# Plant.net
KiCad netlist of a schematic drawn in Altium Designer
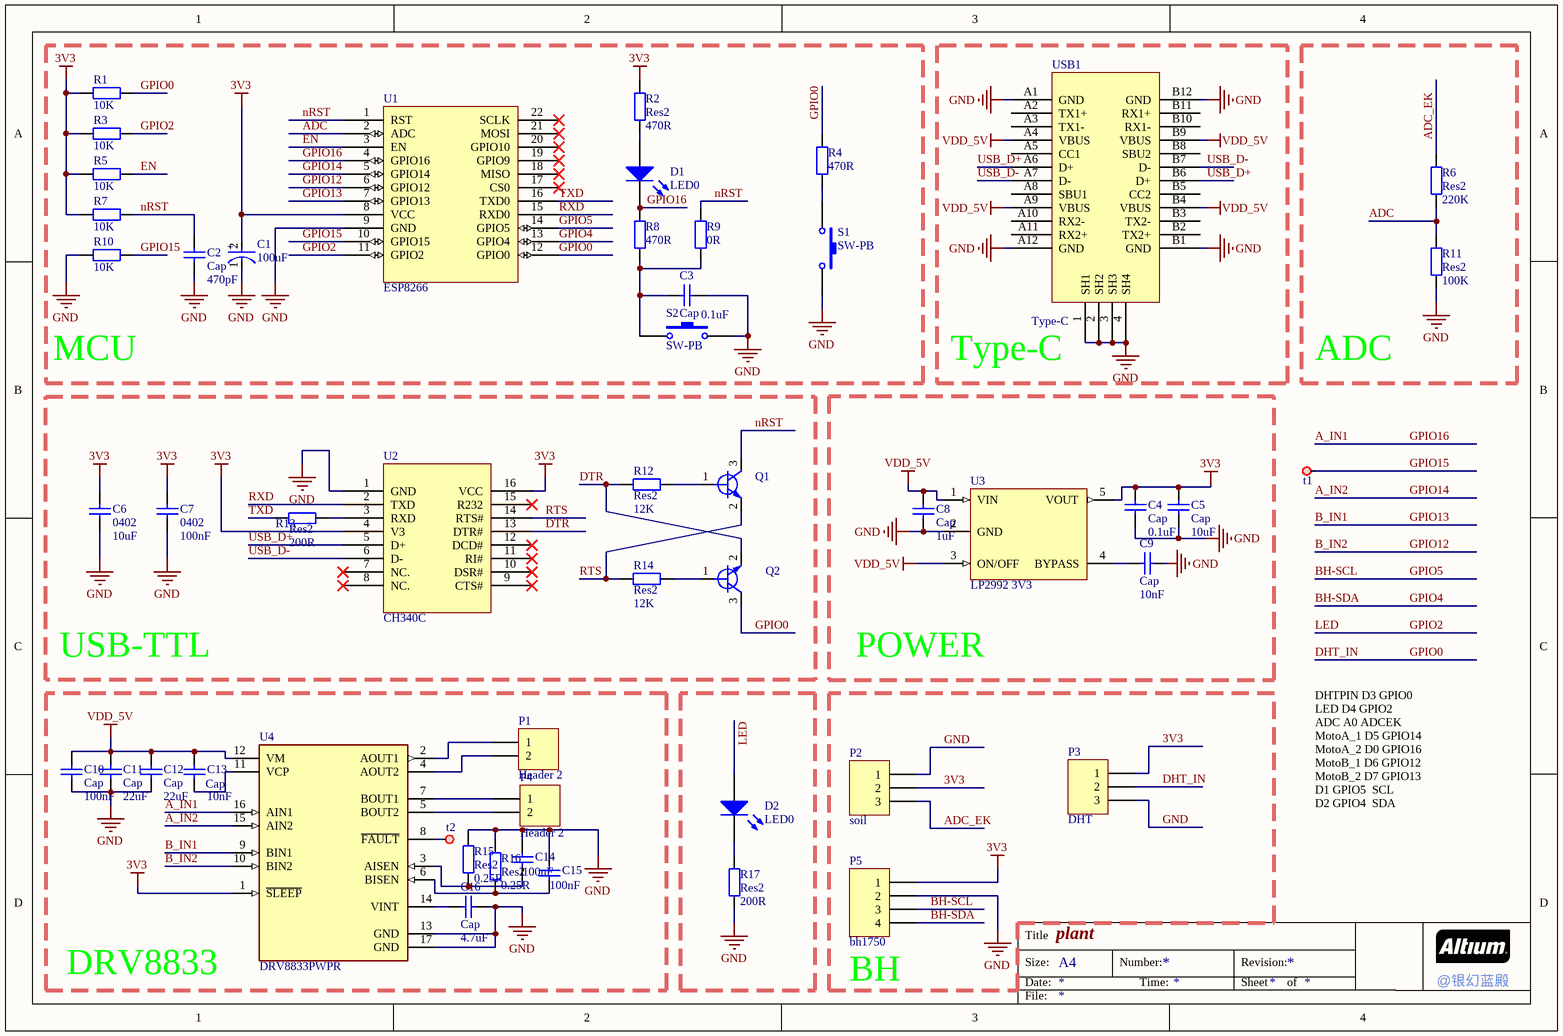
[diagram p0: Plant.SchDoc]

(export (version "E")
  (design (tool "Eeschema 10.0.6"))
  (components
    (comp (ref "C1")
      (value "100uF")
      (footprint "FP-T495D107K016ATE125-MFG")
      (description "CAP TANT 100UF 10% 16V 2917")
      (fields (field (name "VOLTAGE") "16V") (field (name "TOLERANCE") "10%"))
      (libsource (lib "Altium Content Vault") (part "a00bbbee19879c290e62620ae7e47b1"))
    )
    (comp (ref "C2")
      (value "Cap")
      (footprint "Plant:C 0402_M")
      (description "Capacitor (Semiconductor SIM Model)")
      (fields (field (name "ALTIUM_VALUE") "470pF") (field (name "PUBLISHER") "Altium Limited"))
      (libsource (lib "Miscellaneous Devices") (part "Cap Semi"))
    )
    (comp (ref "C3")
      (value "Cap")
      (footprint "Plant:C 0402_M")
      (description "Capacitor (Semiconductor SIM Model)")
      (fields (field (name "ALTIUM_VALUE") "0.1uF") (field (name "PUBLISHER") "Altium Limited"))
      (libsource (lib "Miscellaneous Devices") (part "Cap Semi"))
    )
    (comp (ref "C4")
      (value "Cap")
      (footprint "Plant:C 0402_M")
      (description "Capacitor (Semiconductor SIM Model)")
      (fields (field (name "ALTIUM_VALUE") "0.1uF") (field (name "PUBLISHER") "Altium Limited"))
      (libsource (lib "Miscellaneous Devices") (part "Cap Semi"))
    )
    (comp (ref "C5")
      (value "Cap")
      (footprint "Plant:C 0402_M")
      (description "Capacitor (Semiconductor SIM Model)")
      (fields (field (name "ALTIUM_VALUE") "10uF") (field (name "PUBLISHER") "Altium Limited"))
      (libsource (lib "Miscellaneous Devices") (part "Cap Semi"))
    )
    (comp (ref "C6")
      (value "0402")
      (footprint "Plant:C 0402_M")
      (description "Capacitor (Semiconductor SIM Model)")
      (fields (field (name "ALTIUM_VALUE") "10uF") (field (name "PUBLISHER") "Altium Limited"))
      (libsource (lib "Miscellaneous Devices") (part "Cap Semi"))
    )
    (comp (ref "C7")
      (value "0402")
      (footprint "Plant:C 0402_M")
      (description "Capacitor (Semiconductor SIM Model)")
      (fields (field (name "ALTIUM_VALUE") "100nF") (field (name "PUBLISHER") "Altium Limited"))
      (libsource (lib "Miscellaneous Devices") (part "Cap Semi"))
    )
    (comp (ref "C8")
      (value "Cap")
      (footprint "Plant:C 0402_M")
      (description "Capacitor (Semiconductor SIM Model)")
      (fields (field (name "ALTIUM_VALUE") "1uF") (field (name "PUBLISHER") "Altium Limited"))
      (libsource (lib "Miscellaneous Devices") (part "Cap Semi"))
    )
    (comp (ref "C9")
      (value "Cap")
      (footprint "Plant:C 0402_M")
      (description "Capacitor (Semiconductor SIM Model)")
      (fields (field (name "ALTIUM_VALUE") "10nF") (field (name "PUBLISHER") "Altium Limited"))
      (libsource (lib "Miscellaneous Devices") (part "Cap Semi"))
    )
    (comp (ref "C10")
      (value "Cap")
      (footprint "Plant:C 0402_M")
      (description "Capacitor (Semiconductor SIM Model)")
      (fields (field (name "ALTIUM_VALUE") "100nF") (field (name "PUBLISHER") "Altium Limited"))
      (libsource (lib "Miscellaneous Devices") (part "Cap Semi"))
    )
    (comp (ref "C11")
      (value "Cap")
      (footprint "Plant:C 0402_M")
      (description "Capacitor (Semiconductor SIM Model)")
      (fields (field (name "ALTIUM_VALUE") "22uF") (field (name "PUBLISHER") "Altium Limited"))
      (libsource (lib "Miscellaneous Devices") (part "Cap Semi"))
    )
    (comp (ref "C12")
      (value "Cap")
      (footprint "Plant:C 0402_M")
      (description "Capacitor (Semiconductor SIM Model)")
      (fields (field (name "ALTIUM_VALUE") "22uF") (field (name "PUBLISHER") "Altium Limited"))
      (libsource (lib "Miscellaneous Devices") (part "Cap Semi"))
    )
    (comp (ref "C13")
      (value "Cap")
      (footprint "Plant:C 0402_M")
      (description "Capacitor (Semiconductor SIM Model)")
      (fields (field (name "ALTIUM_VALUE") "10nF") (field (name "PUBLISHER") "Altium Limited"))
      (libsource (lib "Miscellaneous Devices") (part "Cap Semi"))
    )
    (comp (ref "C14")
      (value "100nF")
      (footprint "Plant:C 0402_M")
      (description "Capacitor (Semiconductor SIM Model)")
      (fields (field (name "PUBLISHER") "Altium Limited"))
      (libsource (lib "Miscellaneous Devices") (part "Cap Semi"))
    )
    (comp (ref "C15")
      (value "100nF")
      (footprint "Plant:C 0402_M")
      (description "Capacitor (Semiconductor SIM Model)")
      (fields (field (name "PUBLISHER") "Altium Limited"))
      (libsource (lib "Miscellaneous Devices") (part "Cap Semi"))
    )
    (comp (ref "C16")
      (value "Cap")
      (footprint "Plant:C 0402_M")
      (description "Capacitor (Semiconductor SIM Model)")
      (fields (field (name "ALTIUM_VALUE") "4.7uF") (field (name "PUBLISHER") "Altium Limited"))
      (libsource (lib "Miscellaneous Devices") (part "Cap Semi"))
    )
    (comp (ref "D1")
      (value "LED0")
      (footprint "LED 0603R")
      (description "Typical INFRARED GaAs LED")
      (fields (field (name "PUBLISHER") "Altium Limited"))
      (libsource (lib "Miscellaneous Devices") (part "LED0"))
    )
    (comp (ref "D2")
      (value "LED0")
      (footprint "LED 0603R")
      (description "Typical INFRARED GaAs LED")
      (fields (field (name "PUBLISHER") "Altium Limited"))
      (libsource (lib "Miscellaneous Devices") (part "LED0"))
    )
    (comp (ref "P1")
      (value "Header 2")
      (footprint "HDR1X2")
      (description "Header, 2-Pin")
      (fields (field (name "PUBLISHER") "Altium Limited"))
      (libsource (lib "Miscellaneous Connectors") (part "Header 2"))
    )
    (comp (ref "P2")
      (value "soil")
      (footprint "HDR1X3")
      (description "Header, 3-Pin")
      (fields (field (name "PUBLISHER") "Altium Limited"))
      (libsource (lib "Miscellaneous Connectors") (part "Header 3"))
    )
    (comp (ref "P3")
      (value "DHT")
      (footprint "HDR1X3")
      (description "Header, 3-Pin")
      (fields (field (name "PUBLISHER") "Altium Limited"))
      (libsource (lib "Miscellaneous Connectors") (part "Header 3"))
    )
    (comp (ref "P4")
      (value "Header 2")
      (footprint "HDR1X2")
      (description "Header, 2-Pin")
      (fields (field (name "PUBLISHER") "Altium Limited"))
      (libsource (lib "Miscellaneous Connectors") (part "Header 2"))
    )
    (comp (ref "P5")
      (value "bh1750")
      (footprint "HDR1X4")
      (description "Header, 4-Pin")
      (fields (field (name "PUBLISHER") "Altium Limited"))
      (libsource (lib "Miscellaneous Connectors") (part "Header 4"))
    )
    (comp (ref "Q1")
      (value "Y1 NPN SOT23-3")
      (footprint "SMT_TRIODE_NPN")
      (libsource (lib "DDJ_20180904_Library") (part "S8050"))
    )
    (comp (ref "Q2")
      (value "Y1 NPN SOT23-3")
      (footprint "SMT_TRIODE_NPN")
      (libsource (lib "DDJ_20180904_Library") (part "S8050"))
    )
    (comp (ref "R1")
      (value "10K")
      (footprint "Plant:R 0402_M")
      (description "Resistor")
      (fields (field (name "Comment") "0402") (field (name "PUBLISHER") "Altium Limited"))
      (libsource (lib "") (part "Res2_1"))
    )
    (comp (ref "R2")
      (value "Res2")
      (footprint "Plant:R 0402_M")
      (description "Resistor")
      (fields (field (name "ALTIUM_VALUE") "470R") (field (name "PUBLISHER") "Altium Limited"))
      (libsource (lib "Miscellaneous Devices") (part "Res2"))
    )
    (comp (ref "R3")
      (value "10K")
      (footprint "Plant:R 0402_M")
      (description "Resistor")
      (fields (field (name "Comment") "0402") (field (name "PUBLISHER") "Altium Limited"))
      (libsource (lib "") (part "Res2_1"))
    )
    (comp (ref "R4")
      (value "470R")
      (footprint "Plant:R 0402_M")
      (description "Resistor")
      (fields (field (name "Comment") "Res2") (field (name "PUBLISHER") "Altium Limited"))
      (libsource (lib "") (part "Res2_2"))
    )
    (comp (ref "R5")
      (value "10K")
      (footprint "Plant:R 0402_M")
      (description "Resistor")
      (fields (field (name "Comment") "0402") (field (name "PUBLISHER") "Altium Limited"))
      (libsource (lib "") (part "Res2_1"))
    )
    (comp (ref "R6")
      (value "Res2")
      (footprint "Plant:R 0402_M")
      (description "Resistor")
      (fields (field (name "ALTIUM_VALUE") "220K") (field (name "PUBLISHER") "Altium Limited"))
      (libsource (lib "Miscellaneous Devices") (part "Res2"))
    )
    (comp (ref "R7")
      (value "10K")
      (footprint "Plant:R 0402_M")
      (description "Resistor")
      (fields (field (name "Comment") "0402") (field (name "PUBLISHER") "Altium Limited"))
      (libsource (lib "") (part "Res2_1"))
    )
    (comp (ref "R8")
      (value "470R")
      (footprint "Plant:R 0402_M")
      (description "Resistor")
      (fields (field (name "Comment") "Res2") (field (name "PUBLISHER") "Altium Limited"))
      (libsource (lib "") (part "Res2_2"))
    )
    (comp (ref "R9")
      (value "0R")
      (footprint "Plant:R 0402_M")
      (description "Resistor")
      (fields (field (name "Comment") "Res2") (field (name "PUBLISHER") "Altium Limited"))
      (libsource (lib "") (part "Res2_2"))
    )
    (comp (ref "R10")
      (value "10K")
      (footprint "Plant:R 0402_M")
      (description "Resistor")
      (fields (field (name "Comment") "0402") (field (name "PUBLISHER") "Altium Limited"))
      (libsource (lib "") (part "Res2_1"))
    )
    (comp (ref "R11")
      (value "Res2")
      (footprint "Plant:R 0402_M")
      (description "Resistor")
      (fields (field (name "ALTIUM_VALUE") "100K") (field (name "PUBLISHER") "Altium Limited"))
      (libsource (lib "Miscellaneous Devices") (part "Res2"))
    )
    (comp (ref "R12")
      (value "Res2")
      (footprint "Plant:R 0402_M")
      (description "Resistor")
      (fields (field (name "ALTIUM_VALUE") "12K") (field (name "PUBLISHER") "Altium Limited"))
      (libsource (lib "") (part "Res2_1"))
    )
    (comp (ref "R13")
      (value "Res2")
      (footprint "Plant:R 0402_M")
      (description "Resistor")
      (fields (field (name "ALTIUM_VALUE") "200R") (field (name "PUBLISHER") "Altium Limited"))
      (libsource (lib "") (part "Res2_1"))
    )
    (comp (ref "R14")
      (value "Res2")
      (footprint "Plant:R 0402_M")
      (description "Resistor")
      (fields (field (name "ALTIUM_VALUE") "12K") (field (name "PUBLISHER") "Altium Limited"))
      (libsource (lib "") (part "Res2_1"))
    )
    (comp (ref "R15")
      (value "Res2")
      (footprint "Plant:R 1206_M")
      (description "Resistor")
      (fields (field (name "ALTIUM_VALUE") "0.25R") (field (name "PUBLISHER") "Altium Limited"))
      (libsource (lib "") (part "Res2_1"))
    )
    (comp (ref "R16")
      (value "Res2")
      (footprint "Plant:R 1206_M")
      (description "Resistor")
      (fields (field (name "ALTIUM_VALUE") "0.25R") (field (name "PUBLISHER") "Altium Limited"))
      (libsource (lib "") (part "Res2_1"))
    )
    (comp (ref "R17")
      (value "Res2")
      (footprint "Plant:R 0402_M")
      (description "Resistor")
      (fields (field (name "ALTIUM_VALUE") "200R") (field (name "PUBLISHER") "Altium Limited"))
      (libsource (lib "Miscellaneous Devices") (part "Res2"))
    )
    (comp (ref "S1")
      (value "SW-PB")
      (footprint "TSW DIP-6*6*5")
      (description "Switch")
      (fields (field (name "PUBLISHER") "Altium Limited"))
      (libsource (lib "Miscellaneous Devices") (part "SW-PB"))
    )
    (comp (ref "S2")
      (value "SW-PB")
      (footprint "TSW DIP-6*6*5")
      (description "Switch")
      (fields (field (name "PUBLISHER") "Altium Limited"))
      (libsource (lib "Miscellaneous Devices") (part "SW-PB"))
    )
    (comp (ref "t1") (value "test") (footprint "test") (libsource (lib "RC-AE86") (part "test")))
    (comp (ref "t2") (value "test") (footprint "test") (libsource (lib "RC-AE86") (part "test")))
    (comp (ref "U1") (value "ESP8266") (footprint "esp8266") (libsource (lib "HD") (part "ESP8266")))
    (comp (ref "U2") (value "CH340C") (footprint "CH340") (libsource (lib "HD") (part "CH340C")))
    (comp (ref "U3")
      (value "LP2992 3V3")
      (footprint "SOT23-5N")
      (description "LDO")
      (libsource (lib "MyPcbLib") (part "LP2992"))
    )
    (comp (ref "U4")
      (value "DRV8833PWPR")
      (footprint "FP-PWP0016C-IPC_A")
      (description "IC MOTOR DRIVER PAR 16HTSSOP")
      (libsource (lib "Altium Content Vault") (part "bca689d78e207bdabf30b9b31c2f798"))
    )
    (comp (ref "USB1")
      (value "Type-C")
      (footprint "Type-C-TOP")
      (libsource (lib "MainBoard") (part "USB-Type-C-TOP"))
    )
  )
  (nets
    (net (code "1") (name "/ADC") (class "Default")
      (node (ref "R11") (pin "1") (pinfunction "1_1") (pintype "passive"))
      (node (ref "R6") (pin "2") (pinfunction "2_2") (pintype "passive"))
      (node (ref "U1") (pin "2") (pinfunction "ADC_2") (pintype "bidirectional"))
    )
    (net (code "2") (name "/ADC_EK") (class "Default")
      (node (ref "P2") (pin "3") (pinfunction "3_3") (pintype "passive"))
      (node (ref "R6") (pin "1") (pinfunction "1_1") (pintype "passive"))
    )
    (net (code "3") (name "/A_IN1") (class "Default")
      (node (ref "D1") (pin "2") (pinfunction "K_2") (pintype "passive"))
      (node (ref "R8") (pin "2") (pinfunction "2_2") (pintype "passive"))
      (node (ref "U1") (pin "4") (pinfunction "GPIO16_4") (pintype "bidirectional"))
      (node (ref "U4") (pin "16") (pinfunction "AIN1_16") (pintype "input"))
    )
    (net (code "4") (name "/A_IN2") (class "Default")
      (node (ref "U1") (pin "5") (pinfunction "GPIO14_5") (pintype "bidirectional"))
      (node (ref "U4") (pin "15") (pinfunction "AIN2_15") (pintype "input"))
    )
    (net (code "5") (name "/BH-SCL") (class "Default")
      (node (ref "P5") (pin "3") (pinfunction "3_3") (pintype "passive"))
      (node (ref "U1") (pin "14") (pinfunction "GPIO5_14") (pintype "bidirectional"))
    )
    (net (code "6") (name "/BH-SDA") (class "Default")
      (node (ref "P5") (pin "4") (pinfunction "4_4") (pintype "passive"))
      (node (ref "U1") (pin "13") (pinfunction "GPIO4_13") (pintype "bidirectional"))
    )
    (net (code "7") (name "/B_IN1") (class "Default")
      (node (ref "U1") (pin "7") (pinfunction "GPIO13_7") (pintype "bidirectional"))
      (node (ref "U4") (pin "9") (pinfunction "BIN1_9") (pintype "input"))
    )
    (net (code "8") (name "/B_IN2") (class "Default")
      (node (ref "U1") (pin "6") (pinfunction "GPIO12_6") (pintype "bidirectional"))
      (node (ref "U4") (pin "10") (pinfunction "BIN2_10") (pintype "input"))
    )
    (net (code "9") (name "/DHT_IN") (class "Default")
      (node (ref "P3") (pin "2") (pinfunction "2_2") (pintype "passive"))
      (node (ref "Q2") (pin "3") (pinfunction "COLLECTOR_3") (pintype "passive"))
      (node (ref "R1") (pin "2") (pinfunction "2_2") (pintype "passive"))
      (node (ref "R4") (pin "2") (pinfunction "2_2") (pintype "passive"))
      (node (ref "U1") (pin "12") (pinfunction "GPIO0_12") (pintype "bidirectional"))
    )
    (net (code "10") (name "/DTR") (class "Default")
      (node (ref "Q2") (pin "2") (pinfunction "EMITTER_2") (pintype "passive"))
      (node (ref "R12") (pin "1") (pinfunction "1_1") (pintype "passive"))
      (node (ref "U2") (pin "13") (pinfunction "DTR#_13") (pintype "passive"))
    )
    (net (code "11") (name "/EN") (class "Default")
      (node (ref "R5") (pin "2") (pinfunction "2_2") (pintype "passive"))
      (node (ref "U1") (pin "3") (pinfunction "EN_3") (pintype "passive"))
    )
    (net (code "12") (name "/GPIO2") (class "Default")
      (node (ref "D2") (pin "1") (pinfunction "A_1") (pintype "passive"))
      (node (ref "R3") (pin "2") (pinfunction "2_2") (pintype "passive"))
      (node (ref "U1") (pin "11") (pinfunction "GPIO2_11") (pintype "bidirectional"))
    )
    (net (code "13") (name "/GPIO15") (class "Default")
      (node (ref "R10") (pin "2") (pinfunction "2_2") (pintype "passive"))
      (node (ref "U1") (pin "10") (pinfunction "GPIO15_10") (pintype "bidirectional"))
      (node (ref "t1") (pin "1") (pinfunction "test_1") (pintype "passive"))
    )
    (net (code "14") (name "/RTS") (class "Default")
      (node (ref "Q1") (pin "2") (pinfunction "EMITTER_2") (pintype "passive"))
      (node (ref "R14") (pin "1") (pinfunction "1_1") (pintype "passive"))
      (node (ref "U2") (pin "14") (pinfunction "RTS#_14") (pintype "passive"))
    )
    (net (code "15") (name "/RXD") (class "Default")
      (node (ref "U1") (pin "15") (pinfunction "RXD0_15") (pintype "passive"))
      (node (ref "U2") (pin "2") (pinfunction "TXD_2") (pintype "passive"))
    )
    (net (code "16") (name "/TXD") (class "Default")
      (node (ref "R13") (pin "1") (pinfunction "1_1") (pintype "passive"))
      (node (ref "U1") (pin "16") (pinfunction "TXD0_16") (pintype "passive"))
    )
    (net (code "17") (name "/USB_D+") (class "Default")
      (node (ref "U2") (pin "5") (pinfunction "D+_5") (pintype "passive"))
      (node (ref "USB1") (pin "A6") (pinfunction "D+_A6") (pintype "passive"))
      (node (ref "USB1") (pin "B6") (pinfunction "D+_B6") (pintype "passive"))
    )
    (net (code "18") (name "/USB_D-") (class "Default")
      (node (ref "U2") (pin "6") (pinfunction "D-_6") (pintype "passive"))
      (node (ref "USB1") (pin "A7") (pinfunction "D-_A7") (pintype "passive"))
      (node (ref "USB1") (pin "B7") (pinfunction "D-_B7") (pintype "passive"))
    )
    (net (code "19") (name "/nRST") (class "Default")
      (node (ref "C2") (pin "1") (pinfunction "1_1") (pintype "passive"))
      (node (ref "Q1") (pin "3") (pinfunction "COLLECTOR_3") (pintype "passive"))
      (node (ref "R7") (pin "2") (pinfunction "2_2") (pintype "passive"))
      (node (ref "R9") (pin "2") (pinfunction "2_2") (pintype "passive"))
      (node (ref "U1") (pin "1") (pinfunction "RST_1") (pintype "passive"))
    )
    (net (code "20") (name "3V3") (class "Default")
      (node (ref "C1") (pin "2") (pinfunction "A_2") (pintype "passive"))
      (node (ref "C4") (pin "1") (pinfunction "1_1") (pintype "passive"))
      (node (ref "C5") (pin "1") (pinfunction "1_1") (pintype "passive"))
      (node (ref "C6") (pin "2") (pinfunction "2_2") (pintype "passive"))
      (node (ref "C7") (pin "2") (pinfunction "2_2") (pintype "passive"))
      (node (ref "P2") (pin "2") (pinfunction "2_2") (pintype "passive"))
      (node (ref "P3") (pin "1") (pinfunction "1_1") (pintype "passive"))
      (node (ref "P5") (pin "1") (pinfunction "1_1") (pintype "passive"))
      (node (ref "R1") (pin "1") (pinfunction "1_1") (pintype "passive"))
      (node (ref "R2") (pin "1") (pinfunction "1_1") (pintype "passive"))
      (node (ref "R3") (pin "1") (pinfunction "1_1") (pintype "passive"))
      (node (ref "R5") (pin "1") (pinfunction "1_1") (pintype "passive"))
      (node (ref "R7") (pin "1") (pinfunction "1_1") (pintype "passive"))
      (node (ref "U1") (pin "8") (pinfunction "VCC_8") (pintype "passive"))
      (node (ref "U2") (pin "16") (pinfunction "VCC_16") (pintype "passive"))
      (node (ref "U2") (pin "4") (pinfunction "V3_4") (pintype "passive"))
      (node (ref "U3") (pin "5") (pinfunction "VOUT_5") (pintype "output"))
      (node (ref "U4") (pin "1") (pinfunction "~{SLEEP}_1") (pintype "input"))
    )
    (net (code "21") (name "GND") (class "Default")
      (node (ref "C1") (pin "1") (pinfunction "C_1") (pintype "passive"))
      (node (ref "C10") (pin "2") (pinfunction "2_2") (pintype "passive"))
      (node (ref "C11") (pin "2") (pinfunction "2_2") (pintype "passive"))
      (node (ref "C12") (pin "2") (pinfunction "2_2") (pintype "passive"))
      (node (ref "C14") (pin "2") (pinfunction "2_2") (pintype "passive"))
      (node (ref "C15") (pin "2") (pinfunction "2_2") (pintype "passive"))
      (node (ref "C16") (pin "1") (pinfunction "1_1") (pintype "passive"))
      (node (ref "C2") (pin "2") (pinfunction "2_2") (pintype "passive"))
      (node (ref "C3") (pin "2") (pinfunction "2_2") (pintype "passive"))
      (node (ref "C4") (pin "2") (pinfunction "2_2") (pintype "passive"))
      (node (ref "C5") (pin "2") (pinfunction "2_2") (pintype "passive"))
      (node (ref "C6") (pin "1") (pinfunction "1_1") (pintype "passive"))
      (node (ref "C7") (pin "1") (pinfunction "1_1") (pintype "passive"))
      (node (ref "C8") (pin "2") (pinfunction "2_2") (pintype "passive"))
      (node (ref "C9") (pin "2") (pinfunction "2_2") (pintype "passive"))
      (node (ref "P2") (pin "1") (pinfunction "1_1") (pintype "passive"))
      (node (ref "P3") (pin "3") (pinfunction "3_3") (pintype "passive"))
      (node (ref "P5") (pin "2") (pinfunction "2_2") (pintype "passive"))
      (node (ref "R10") (pin "1") (pinfunction "1_1") (pintype "passive"))
      (node (ref "R11") (pin "2") (pinfunction "2_2") (pintype "passive"))
      (node (ref "R15") (pin "2") (pinfunction "2_2") (pintype "passive"))
      (node (ref "R16") (pin "2") (pinfunction "2_2") (pintype "passive"))
      (node (ref "R17") (pin "2") (pinfunction "2_2") (pintype "passive"))
      (node (ref "S1") (pin "2") (pinfunction "2_2") (pintype "passive"))
      (node (ref "S2") (pin "2") (pinfunction "2_2") (pintype "passive"))
      (node (ref "U1") (pin "9") (pinfunction "GND_9") (pintype "passive"))
      (node (ref "U2") (pin "1") (pinfunction "GND_1") (pintype "passive"))
      (node (ref "U3") (pin "2") (pinfunction "GND_2") (pintype "passive"))
      (node (ref "U4") (pin "13") (pinfunction "GND_13") (pintype "power_in"))
      (node (ref "U4") (pin "17") (pinfunction "GND_17") (pintype "power_in"))
      (node (ref "USB1") (pin "1") (pinfunction "SH1_1") (pintype "passive"))
      (node (ref "USB1") (pin "2") (pinfunction "SH2_2") (pintype "passive"))
      (node (ref "USB1") (pin "3") (pinfunction "SH3_3") (pintype "passive"))
      (node (ref "USB1") (pin "4") (pinfunction "SH4_4") (pintype "passive"))
      (node (ref "USB1") (pin "A1") (pinfunction "GND_A1") (pintype "passive"))
      (node (ref "USB1") (pin "A12") (pinfunction "GND_A12") (pintype "passive"))
      (node (ref "USB1") (pin "B1") (pinfunction "GND_B1") (pintype "passive"))
      (node (ref "USB1") (pin "B12") (pinfunction "GND_B12") (pintype "passive"))
    )
    (net (code "22") (name "Net-(C3-Pad1)") (class "Default")
      (node (ref "C3") (pin "1") (pinfunction "1_1") (pintype "passive"))
      (node (ref "R8") (pin "1") (pinfunction "1_1") (pintype "passive"))
      (node (ref "R9") (pin "1") (pinfunction "1_1") (pintype "passive"))
      (node (ref "S2") (pin "1") (pinfunction "1_1") (pintype "passive"))
    )
    (net (code "23") (name "Net-(D1-A)") (class "Default")
      (node (ref "D1") (pin "1") (pinfunction "A_1") (pintype "passive"))
      (node (ref "R2") (pin "2") (pinfunction "2_2") (pintype "passive"))
    )
    (net (code "24") (name "Net-(D2-K)") (class "Default")
      (node (ref "D2") (pin "2") (pinfunction "K_2") (pintype "passive"))
      (node (ref "R17") (pin "1") (pinfunction "1_1") (pintype "passive"))
    )
    (net (code "25") (name "Net-(Q1-BASE)") (class "Default")
      (node (ref "Q1") (pin "1") (pinfunction "BASE_1") (pintype "passive"))
      (node (ref "R12") (pin "2") (pinfunction "2_2") (pintype "passive"))
    )
    (net (code "26") (name "Net-(Q2-BASE)") (class "Default")
      (node (ref "Q2") (pin "1") (pinfunction "BASE_1") (pintype "passive"))
      (node (ref "R14") (pin "2") (pinfunction "2_2") (pintype "passive"))
    )
    (net (code "27") (name "Net-(R4-Pad1)") (class "Default")
      (node (ref "R4") (pin "1") (pinfunction "1_1") (pintype "passive"))
      (node (ref "S1") (pin "1") (pinfunction "1_1") (pintype "passive"))
    )
    (net (code "28") (name "Net-(U2-RXD)") (class "Default")
      (node (ref "R13") (pin "2") (pinfunction "2_2") (pintype "passive"))
      (node (ref "U2") (pin "3") (pinfunction "RXD_3") (pintype "passive"))
    )
    (net (code "29") (name "Net-(U3-BYPASS)") (class "Default")
      (node (ref "C9") (pin "1") (pinfunction "1_1") (pintype "passive"))
      (node (ref "U3") (pin "4") (pinfunction "BYPASS_4") (pintype "passive"))
    )
    (net (code "30") (name "Net-(U4-AISEN)") (class "Default")
      (node (ref "C14") (pin "1") (pinfunction "1_1") (pintype "passive"))
      (node (ref "R15") (pin "1") (pinfunction "1_1") (pintype "passive"))
      (node (ref "U4") (pin "3") (pinfunction "AISEN_3") (pintype "input"))
    )
    (net (code "31") (name "Net-(U4-AOUT1)") (class "Default")
      (node (ref "P1") (pin "1") (pinfunction "1_1") (pintype "passive"))
      (node (ref "U4") (pin "2") (pinfunction "AOUT1_2") (pintype "output"))
    )
    (net (code "32") (name "Net-(U4-AOUT2)") (class "Default")
      (node (ref "P1") (pin "2") (pinfunction "2_2") (pintype "passive"))
      (node (ref "U4") (pin "4") (pinfunction "AOUT2_4") (pintype "tri_state"))
    )
    (net (code "33") (name "Net-(U4-BISEN)") (class "Default")
      (node (ref "C15") (pin "1") (pinfunction "1_1") (pintype "passive"))
      (node (ref "R16") (pin "1") (pinfunction "1_1") (pintype "passive"))
      (node (ref "U4") (pin "6") (pinfunction "BISEN_6") (pintype "input"))
    )
    (net (code "34") (name "Net-(U4-BOUT1)") (class "Default")
      (node (ref "P4") (pin "1") (pinfunction "1_1") (pintype "passive"))
      (node (ref "U4") (pin "7") (pinfunction "BOUT1_7") (pintype "tri_state"))
    )
    (net (code "35") (name "Net-(U4-BOUT2)") (class "Default")
      (node (ref "P4") (pin "2") (pinfunction "2_2") (pintype "passive"))
      (node (ref "U4") (pin "5") (pinfunction "BOUT2_5") (pintype "tri_state"))
    )
    (net (code "36") (name "Net-(U4-VCP)") (class "Default")
      (node (ref "C13") (pin "1") (pinfunction "1_1") (pintype "passive"))
      (node (ref "U4") (pin "11") (pinfunction "VCP_11") (pintype "passive"))
    )
    (net (code "37") (name "Net-(U4-VINT)") (class "Default")
      (node (ref "C16") (pin "2") (pinfunction "2_2") (pintype "passive"))
      (node (ref "U4") (pin "14") (pinfunction "VINT_14") (pintype "power_in"))
    )
    (net (code "38") (name "Net-(U4-~{FAULT})") (class "Default")
      (node (ref "U4") (pin "8") (pinfunction "~{FAULT}_8") (pintype "open_collector"))
      (node (ref "t2") (pin "1") (pinfunction "test_1") (pintype "passive"))
    )
    (net (code "39") (name "VDD_5V") (class "Default")
      (node (ref "C10") (pin "1") (pinfunction "1_1") (pintype "passive"))
      (node (ref "C11") (pin "1") (pinfunction "1_1") (pintype "passive"))
      (node (ref "C12") (pin "1") (pinfunction "1_1") (pintype "passive"))
      (node (ref "C13") (pin "2") (pinfunction "2_2") (pintype "passive"))
      (node (ref "C8") (pin "1") (pinfunction "1_1") (pintype "passive"))
      (node (ref "U3") (pin "1") (pinfunction "VIN_1") (pintype "input"))
      (node (ref "U3") (pin "3") (pinfunction "ON/OFF_3") (pintype "input"))
      (node (ref "U4") (pin "12") (pinfunction "VM_12") (pintype "power_in"))
      (node (ref "USB1") (pin "A4") (pinfunction "VBUS_A4") (pintype "passive"))
      (node (ref "USB1") (pin "A9") (pinfunction "VBUS_A9") (pintype "passive"))
      (node (ref "USB1") (pin "B4") (pinfunction "VBUS_B4") (pintype "passive"))
      (node (ref "USB1") (pin "B9") (pinfunction "VBUS_B9") (pintype "passive"))
    )
    (net (code "40") (name "unconnected-(U1-CS0-Pad17)") (class "Default")
      (node (ref "U1") (pin "17") (pinfunction "CS0_17") (pintype "passive+no_connect"))
    )
    (net (code "41") (name "unconnected-(U1-GPIO9-Pad19)") (class "Default")
      (node (ref "U1") (pin "19") (pinfunction "GPIO9_19") (pintype "passive+no_connect"))
    )
    (net (code "42") (name "unconnected-(U1-GPIO10-Pad20)") (class "Default")
      (node (ref "U1") (pin "20") (pinfunction "GPIO10_20") (pintype "passive+no_connect"))
    )
    (net (code "43") (name "unconnected-(U1-MISO-Pad18)") (class "Default")
      (node (ref "U1") (pin "18") (pinfunction "MISO_18") (pintype "passive+no_connect"))
    )
    (net (code "44") (name "unconnected-(U1-MOSI-Pad21)") (class "Default")
      (node (ref "U1") (pin "21") (pinfunction "MOSI_21") (pintype "passive+no_connect"))
    )
    (net (code "45") (name "unconnected-(U1-SCLK-Pad22)") (class "Default")
      (node (ref "U1") (pin "22") (pinfunction "SCLK_22") (pintype "passive+no_connect"))
    )
    (net (code "46") (name "unconnected-(U2-CTS#-Pad9)") (class "Default")
      (node (ref "U2") (pin "9") (pinfunction "CTS#_9") (pintype "passive+no_connect"))
    )
    (net (code "47") (name "unconnected-(U2-DCD#-Pad12)") (class "Default")
      (node (ref "U2") (pin "12") (pinfunction "DCD#_12") (pintype "passive+no_connect"))
    )
    (net (code "48") (name "unconnected-(U2-DSR#-Pad10)") (class "Default")
      (node (ref "U2") (pin "10") (pinfunction "DSR#_10") (pintype "passive+no_connect"))
    )
    (net (code "49") (name "unconnected-(U2-NC.-Pad7)") (class "Default")
      (node (ref "U2") (pin "7") (pinfunction "NC._7") (pintype "passive+no_connect"))
    )
    (net (code "50") (name "unconnected-(U2-NC.-Pad8)") (class "Default")
      (node (ref "U2") (pin "8") (pinfunction "NC._8") (pintype "passive+no_connect"))
    )
    (net (code "51") (name "unconnected-(U2-R232-Pad15)") (class "Default")
      (node (ref "U2") (pin "15") (pinfunction "R232_15") (pintype "passive+no_connect"))
    )
    (net (code "52") (name "unconnected-(U2-RI#-Pad11)") (class "Default")
      (node (ref "U2") (pin "11") (pinfunction "RI#_11") (pintype "passive+no_connect"))
    )
    (net (code "53") (name "unconnected-(USB1-CC1-PadA5)") (class "Default")
      (node (ref "USB1") (pin "A5") (pinfunction "CC1_A5") (pintype "passive"))
    )
    (net (code "54") (name "unconnected-(USB1-CC2-PadB5)") (class "Default")
      (node (ref "USB1") (pin "B5") (pinfunction "CC2_B5") (pintype "passive"))
    )
    (net (code "55") (name "unconnected-(USB1-RX1+-PadB11)") (class "Default")
      (node (ref "USB1") (pin "B11") (pinfunction "RX1+_B11") (pintype "passive"))
    )
    (net (code "56") (name "unconnected-(USB1-RX1--PadB10)") (class "Default")
      (node (ref "USB1") (pin "B10") (pinfunction "RX1-_B10") (pintype "passive"))
    )
    (net (code "57") (name "unconnected-(USB1-RX2+-PadA11)") (class "Default")
      (node (ref "USB1") (pin "A11") (pinfunction "RX2+_A11") (pintype "passive"))
    )
    (net (code "58") (name "unconnected-(USB1-RX2--PadA10)") (class "Default")
      (node (ref "USB1") (pin "A10") (pinfunction "RX2-_A10") (pintype "passive"))
    )
    (net (code "59") (name "unconnected-(USB1-SBU1-PadA8)") (class "Default")
      (node (ref "USB1") (pin "A8") (pinfunction "SBU1_A8") (pintype "passive"))
    )
    (net (code "60") (name "unconnected-(USB1-SBU2-PadB8)") (class "Default")
      (node (ref "USB1") (pin "B8") (pinfunction "SBU2_B8") (pintype "passive"))
    )
    (net (code "61") (name "unconnected-(USB1-TX1+-PadA2)") (class "Default")
      (node (ref "USB1") (pin "A2") (pinfunction "TX1+_A2") (pintype "passive"))
    )
    (net (code "62") (name "unconnected-(USB1-TX1--PadA3)") (class "Default")
      (node (ref "USB1") (pin "A3") (pinfunction "TX1-_A3") (pintype "passive"))
    )
    (net (code "63") (name "unconnected-(USB1-TX2+-PadB2)") (class "Default")
      (node (ref "USB1") (pin "B2") (pinfunction "TX2+_B2") (pintype "passive"))
    )
    (net (code "64") (name "unconnected-(USB1-TX2--PadB3)") (class "Default")
      (node (ref "USB1") (pin "B3") (pinfunction "TX2-_B3") (pintype "passive"))
    )
  )
)
